# 09_Clock.net
KiCad netlist of a schematic drawn in Altium Designer
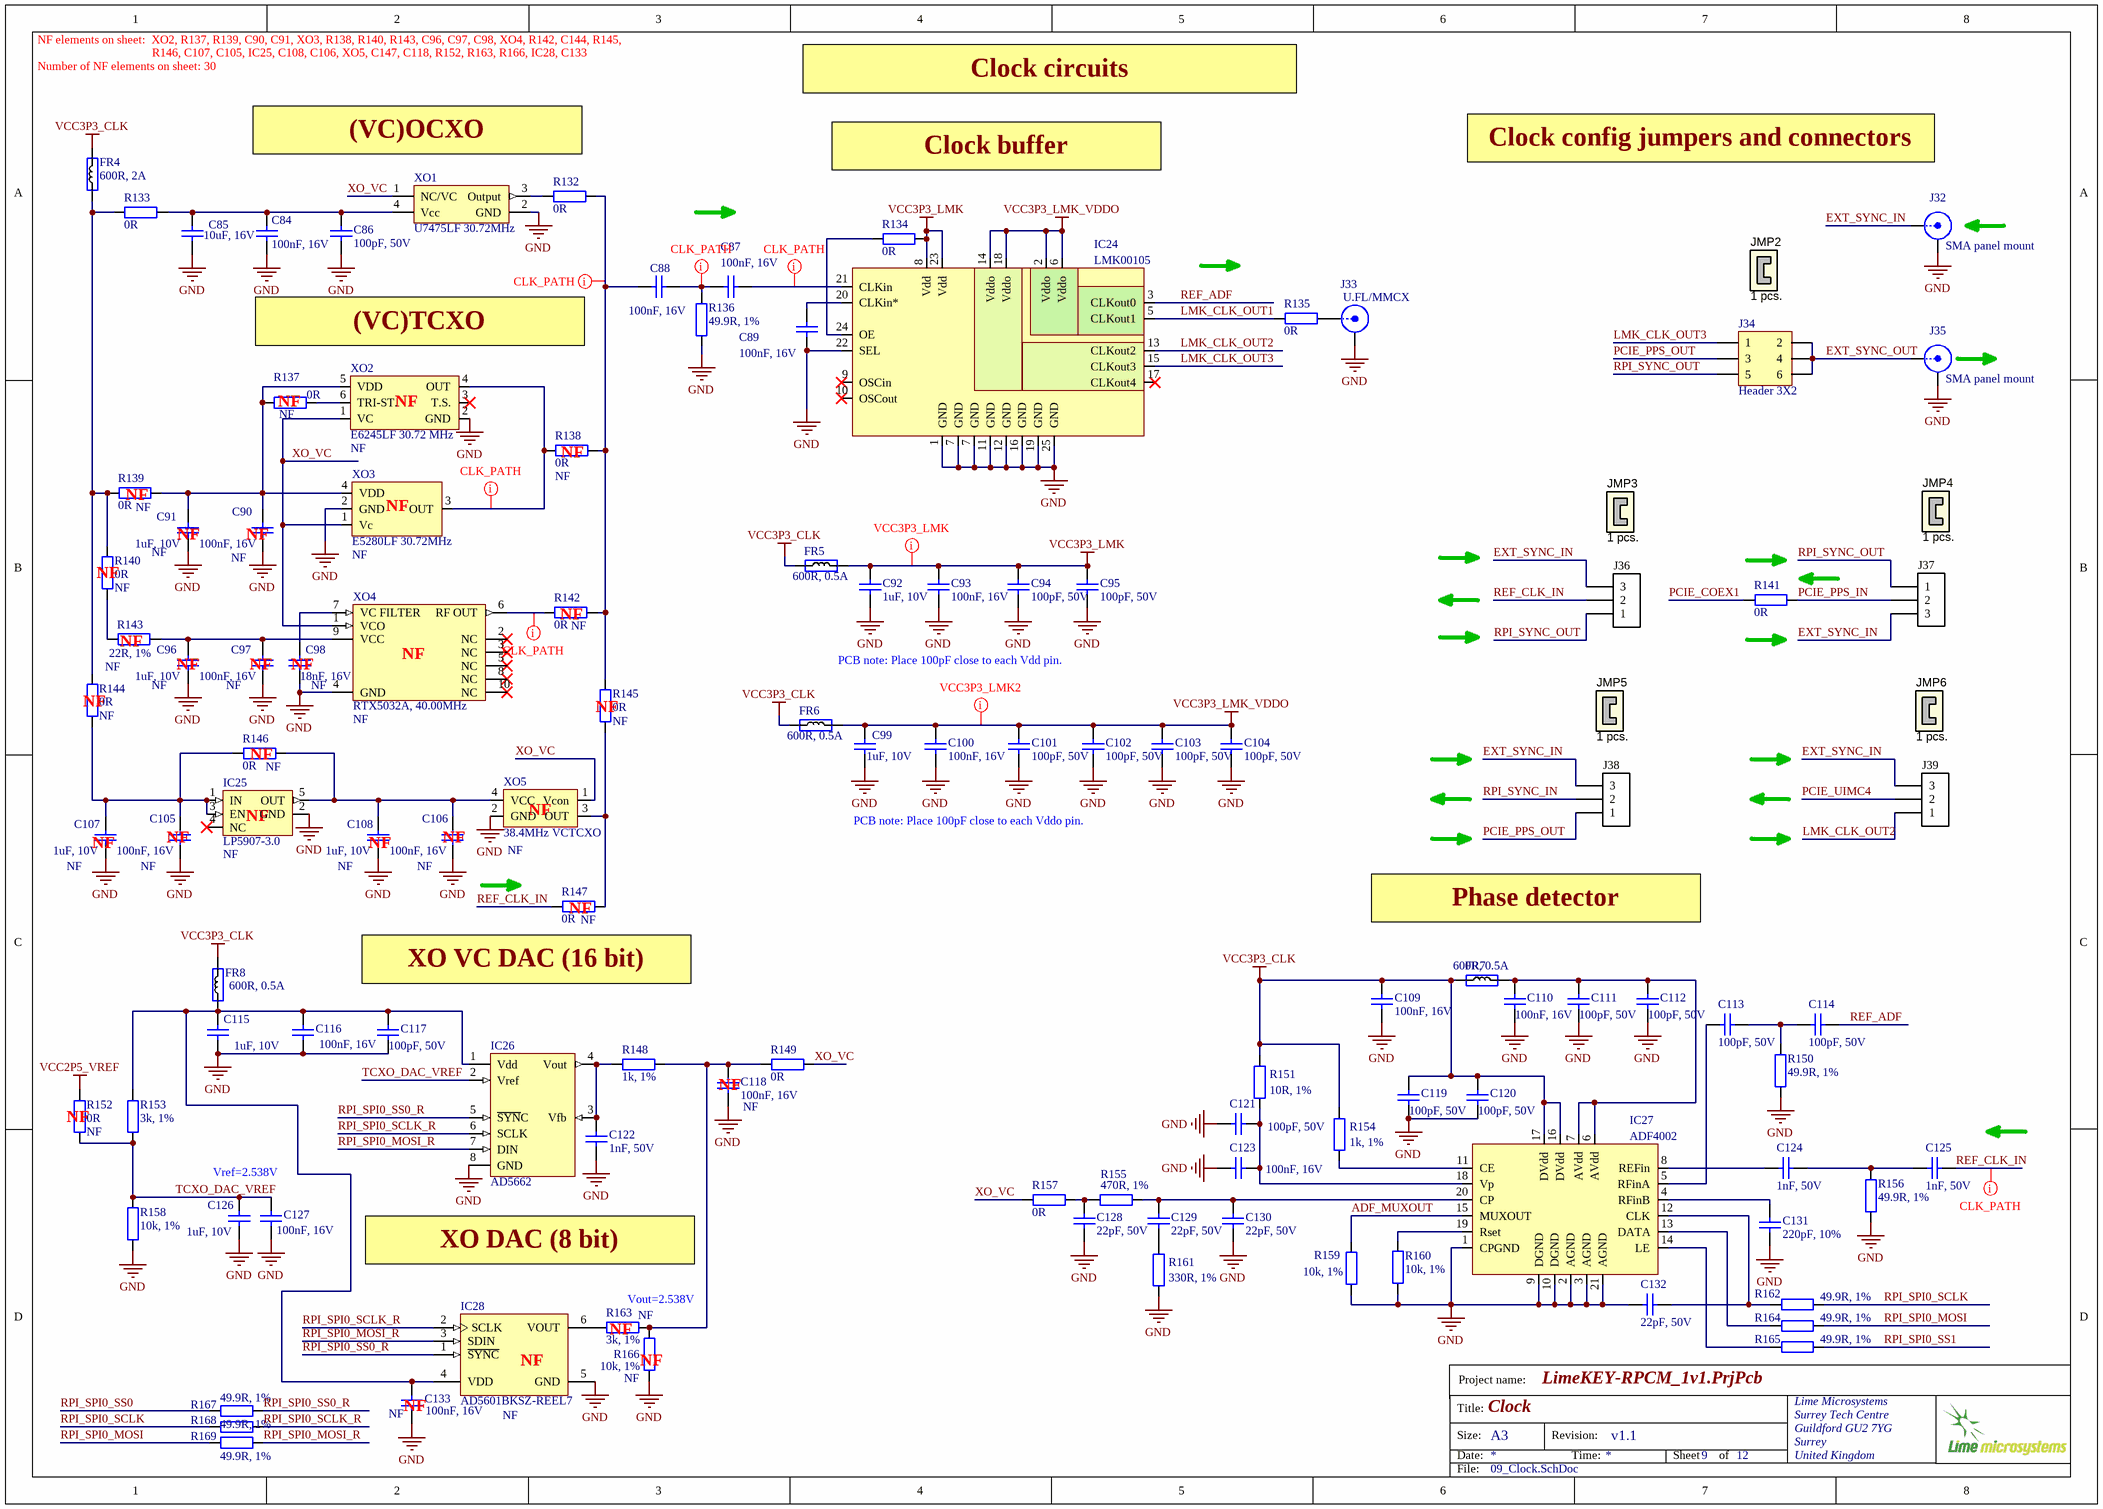
[diagram p0: 09_Clock.SchDoc]

(export (version "E")
  (design (tool "Eeschema 10.0.6"))
  (components
    (comp (ref "C84")
      (value "100nF, 16V")
      (footprint "CAP0402")
      (fields
        (field (name "MANUFACTURER") "Murata Electronics")
        (field (name "TOLERANCE") "10 %")
        (field (name "MANUFACTURER PART NUMBER") "GRM155R71C104KA88D")
      )
      (libsource (lib "LimeMicroAltiumLib_schLib") (part "Cap_0402"))
    )
    (comp (ref "C85")
      (value "10uF, 16V")
      (footprint "CAP0603")
      (fields (field (name "MANUFACTURER") "Yageo") (field (name "TOLERANCE") "±20%"))
      (libsource (lib "LimeMicroAltiumLib_schLib") (part "Cap_0603"))
    )
    (comp (ref "C86")
      (value "100pF, 50V")
      (footprint "CAP0402")
      (fields (field (name "TOLERANCE") "±5%") (field (name "MANUFACTURER") "Yageo"))
      (libsource (lib "LimeMicroAltiumLib_schLib") (part "Cap_0402"))
    )
    (comp (ref "C87")
      (value "100nF, 16V")
      (footprint "CAP0402")
      (fields
        (field (name "MANUFACTURER") "Murata Electronics")
        (field (name "TOLERANCE") "10 %")
        (field (name "MANUFACTURER PART NUMBER") "GRM155R71C104KA88D")
      )
      (libsource (lib "LimeMicroAltiumLib_schLib") (part "Cap_0402"))
    )
    (comp (ref "C88")
      (value "100nF, 16V")
      (footprint "CAP0402")
      (fields
        (field (name "MANUFACTURER") "Murata Electronics")
        (field (name "TOLERANCE") "10 %")
        (field (name "MANUFACTURER PART NUMBER") "GRM155R71C104KA88D")
      )
      (libsource (lib "LimeMicroAltiumLib_schLib") (part "Cap_0402"))
    )
    (comp (ref "C89")
      (value "100nF, 16V")
      (footprint "CAP0402")
      (fields
        (field (name "MANUFACTURER") "Murata Electronics")
        (field (name "TOLERANCE") "10 %")
        (field (name "MANUFACTURER PART NUMBER") "GRM155R71C104KA88D")
      )
      (libsource (lib "LimeMicroAltiumLib_schLib") (part "Cap_0402"))
    )
    (comp (ref "C90")
      (value "100nF, 16V")
      (footprint "CAP0402")
      (fields
        (field (name "ASSEMBLY INFO") "NF")
        (field (name "MANUFACTURER") "Murata Electronics")
        (field (name "TOLERANCE") "10 %")
        (field (name "MANUFACTURER PART NUMBER") "GRM155R71C104KA88D")
      )
      (libsource (lib "LimeMicroAltiumLib_schLib") (part "Cap_0402"))
    )
    (comp (ref "C91")
      (value "1uF, 10V")
      (footprint "CAP0402")
      (description "CAP CER 1UF 10V X5R 0402")
      (fields (field (name "ASSEMBLY INFO") "NF") (field (name "MANUFACTURER") "Yageo"))
      (libsource (lib "LimeMicroAltiumLib_schLib") (part "Cap_0402"))
    )
    (comp (ref "C92")
      (value "1uF, 10V")
      (footprint "CAP0402")
      (description "CAP CER 1UF 10V X5R 0402")
      (fields (field (name "MANUFACTURER") "Yageo") (field (name "TOLERANCE") "±20%"))
      (libsource (lib "LimeMicroAltiumLib_schLib") (part "Cap_0402"))
    )
    (comp (ref "C93")
      (value "100nF, 16V")
      (footprint "CAP0402")
      (fields
        (field (name "MANUFACTURER") "Murata Electronics")
        (field (name "TOLERANCE") "10 %")
        (field (name "MANUFACTURER PART NUMBER") "GRM155R71C104KA88D")
      )
      (libsource (lib "LimeMicroAltiumLib_schLib") (part "Cap_0402"))
    )
    (comp (ref "C94")
      (value "100pF, 50V")
      (footprint "CAP0402")
      (fields (field (name "MANUFACTURER") "Yageo") (field (name "TOLERANCE") "±5%"))
      (libsource (lib "LimeMicroAltiumLib_schLib") (part "Cap_0402"))
    )
    (comp (ref "C95")
      (value "100pF, 50V")
      (footprint "CAP0402")
      (fields (field (name "MANUFACTURER") "Yageo") (field (name "TOLERANCE") "±5%"))
      (libsource (lib "LimeMicroAltiumLib_schLib") (part "Cap_0402"))
    )
    (comp (ref "C96")
      (value "1uF, 10V")
      (footprint "CAP0402")
      (description "CAP CER 1UF 10V X5R 0402")
      (fields (field (name "ASSEMBLY INFO") "NF") (field (name "MANUFACTURER") "Yageo"))
      (libsource (lib "LimeMicroAltiumLib_schLib") (part "Cap_0402"))
    )
    (comp (ref "C97")
      (value "100nF, 16V")
      (footprint "CAP0402")
      (fields
        (field (name "ASSEMBLY INFO") "NF")
        (field (name "MANUFACTURER") "Murata Electronics")
        (field (name "TOLERANCE") "10 %")
        (field (name "MANUFACTURER PART NUMBER") "GRM155R71C104KA88D")
      )
      (libsource (lib "LimeMicroAltiumLib_schLib") (part "Cap_0402"))
    )
    (comp (ref "C98")
      (value "18nF, 16V")
      (footprint "CAP0402")
      (fields
        (field (name "ASSEMBLY INFO") "NF")
        (field (name "MANUFACTURER") "Yageo")
        (field (name "TOLERANCE") "±10%")
      )
      (libsource (lib "LimeMicroAltiumLib_schLib") (part "Cap_0402"))
    )
    (comp (ref "C99")
      (value "1uF, 10V")
      (footprint "CAP0402")
      (description "CAP CER 1UF 10V X5R 0402")
      (fields (field (name "MANUFACTURER") "Yageo") (field (name "TOLERANCE") "±20%"))
      (libsource (lib "LimeMicroAltiumLib_schLib") (part "Cap_0402"))
    )
    (comp (ref "C100")
      (value "100nF, 16V")
      (footprint "CAP0402")
      (fields
        (field (name "MANUFACTURER") "Murata Electronics")
        (field (name "TOLERANCE") "10 %")
        (field (name "MANUFACTURER PART NUMBER") "GRM155R71C104KA88D")
      )
      (libsource (lib "LimeMicroAltiumLib_schLib") (part "Cap_0402"))
    )
    (comp (ref "C101")
      (value "100pF, 50V")
      (footprint "CAP0402")
      (fields (field (name "MANUFACTURER") "Yageo") (field (name "TOLERANCE") "±5%"))
      (libsource (lib "LimeMicroAltiumLib_schLib") (part "Cap_0402"))
    )
    (comp (ref "C102")
      (value "100pF, 50V")
      (footprint "CAP0402")
      (fields (field (name "MANUFACTURER") "Yageo") (field (name "TOLERANCE") "±5%"))
      (libsource (lib "LimeMicroAltiumLib_schLib") (part "Cap_0402"))
    )
    (comp (ref "C103")
      (value "100pF, 50V")
      (footprint "CAP0402")
      (fields (field (name "MANUFACTURER") "Yageo") (field (name "TOLERANCE") "±5%"))
      (libsource (lib "LimeMicroAltiumLib_schLib") (part "Cap_0402"))
    )
    (comp (ref "C104")
      (value "100pF, 50V")
      (footprint "CAP0402")
      (fields (field (name "MANUFACTURER") "Yageo") (field (name "TOLERANCE") "±5%"))
      (libsource (lib "LimeMicroAltiumLib_schLib") (part "Cap_0402"))
    )
    (comp (ref "C105")
      (value "100nF, 16V")
      (footprint "CAP0402")
      (fields
        (field (name "ASSEMBLY INFO") "NF")
        (field (name "MANUFACTURER") "Murata Electronics")
        (field (name "TOLERANCE") "10 %")
        (field (name "MANUFACTURER PART NUMBER") "GRM155R71C104KA88D")
      )
      (libsource (lib "") (part "Cap_0402_1"))
    )
    (comp (ref "C106")
      (value "100nF, 16V")
      (footprint "CAP0402")
      (fields
        (field (name "ASSEMBLY INFO") "NF")
        (field (name "MANUFACTURER") "Murata Electronics")
        (field (name "TOLERANCE") "10 %")
        (field (name "MANUFACTURER PART NUMBER") "GRM155R71C104KA88D")
      )
      (libsource (lib "") (part "Cap_0402_1"))
    )
    (comp (ref "C107")
      (value "1uF, 10V")
      (footprint "CAP0402")
      (fields (field (name "ASSEMBLY INFO") "NF") (field (name "MANUFACTURER") "Yageo"))
      (libsource (lib "") (part "Cap_0402_1"))
    )
    (comp (ref "C108")
      (value "1uF, 10V")
      (footprint "CAP0402")
      (fields (field (name "ASSEMBLY INFO") "NF") (field (name "MANUFACTURER") "Yageo"))
      (libsource (lib "") (part "Cap_0402_1"))
    )
    (comp (ref "C109")
      (value "100nF, 16V")
      (footprint "CAP0402")
      (fields
        (field (name "MANUFACTURER") "Murata Electronics")
        (field (name "TOLERANCE") "10 %")
        (field (name "MANUFACTURER PART NUMBER") "GRM155R71C104KA88D")
      )
      (libsource (lib "LimeMicroAltiumLib_schLib") (part "Cap_0402"))
    )
    (comp (ref "C110")
      (value "100nF, 16V")
      (footprint "CAP0402")
      (fields
        (field (name "MANUFACTURER") "Murata Electronics")
        (field (name "TOLERANCE") "10 %")
        (field (name "MANUFACTURER PART NUMBER") "GRM155R71C104KA88D")
      )
      (libsource (lib "LimeMicroAltiumLib_schLib") (part "Cap_0402"))
    )
    (comp (ref "C111")
      (value "100pF, 50V")
      (footprint "CAP0402")
      (fields (field (name "MANUFACTURER") "Yageo") (field (name "TOLERANCE") "±5%"))
      (libsource (lib "LimeMicroAltiumLib_schLib") (part "Cap_0402"))
    )
    (comp (ref "C112")
      (value "100pF, 50V")
      (footprint "CAP0402")
      (fields (field (name "MANUFACTURER") "Yageo") (field (name "TOLERANCE") "±5%"))
      (libsource (lib "LimeMicroAltiumLib_schLib") (part "Cap_0402"))
    )
    (comp (ref "C113")
      (value "100pF, 50V")
      (footprint "CAP0402")
      (fields (field (name "MANUFACTURER") "Yageo") (field (name "TOLERANCE") "±5%"))
      (libsource (lib "LimeMicroAltiumLib_schLib") (part "Cap_0402"))
    )
    (comp (ref "C114")
      (value "100pF, 50V")
      (footprint "CAP0402")
      (fields (field (name "MANUFACTURER") "Yageo") (field (name "TOLERANCE") "±5%"))
      (libsource (lib "LimeMicroAltiumLib_schLib") (part "Cap_0402"))
    )
    (comp (ref "C115")
      (value "1uF, 10V")
      (footprint "CAP0402")
      (description "CAP CER 1UF 10V X5R 0402")
      (fields (field (name "MANUFACTURER") "Yageo") (field (name "TOLERANCE") "±20%"))
      (libsource (lib "LimeMicroAltiumLib_schLib") (part "Cap_0402"))
    )
    (comp (ref "C116")
      (value "100nF, 16V")
      (footprint "CAP0402")
      (fields
        (field (name "TOLERANCE") "10 %")
        (field (name "MANUFACTURER") "Murata Electronics")
        (field (name "MANUFACTURER PART NUMBER") "GRM155R71C104KA88D")
      )
      (libsource (lib "LimeFPGAboard_schLib") (part "Cap_0603"))
    )
    (comp (ref "C117")
      (value "100pF, 50V")
      (footprint "CAP0402")
      (fields (field (name "MANUFACTURER") "Yageo") (field (name "TOLERANCE") "±5%"))
      (libsource (lib "LimeMicroAltiumLib_schLib") (part "Cap_0402"))
    )
    (comp (ref "C118")
      (value "100nF, 16V")
      (footprint "CAP0402")
      (fields
        (field (name "ASSEMBLY INFO") "NF")
        (field (name "MANUFACTURER") "Murata Electronics")
        (field (name "TOLERANCE") "10 %")
        (field (name "MANUFACTURER PART NUMBER") "GRM155R71C104KA88D")
      )
      (libsource (lib "LimeMicroAltiumLib_schLib") (part "Cap_0402"))
    )
    (comp (ref "C119")
      (value "100pF, 50V")
      (footprint "CAP0402")
      (fields (field (name "MANUFACTURER") "Yageo") (field (name "TOLERANCE") "±5%"))
      (libsource (lib "LimeMicroAltiumLib_schLib") (part "Cap_0402"))
    )
    (comp (ref "C120")
      (value "100pF, 50V")
      (footprint "CAP0402")
      (fields (field (name "MANUFACTURER") "Yageo") (field (name "TOLERANCE") "±5%"))
      (libsource (lib "LimeMicroAltiumLib_schLib") (part "Cap_0402"))
    )
    (comp (ref "C121")
      (value "100pF, 50V")
      (footprint "CAP0402")
      (fields (field (name "MANUFACTURER") "Yageo") (field (name "TOLERANCE") "±5%"))
      (libsource (lib "LimeMicroAltiumLib_schLib") (part "Cap_0402"))
    )
    (comp (ref "C122")
      (value "1nF, 50V")
      (footprint "CAP0402")
      (fields
        (field (name "TOLERANCE") "±10%")
        (field (name "MANUFACTURER") "Murata Electronics North America")
      )
      (libsource (lib "LimeMicroAltiumLib_schLib") (part "Cap_0402"))
    )
    (comp (ref "C123")
      (value "100nF, 16V")
      (footprint "CAP0402")
      (fields
        (field (name "MANUFACTURER") "Murata Electronics")
        (field (name "TOLERANCE") "10 %")
        (field (name "MANUFACTURER PART NUMBER") "GRM155R71C104KA88D")
      )
      (libsource (lib "LimeMicroAltiumLib_schLib") (part "Cap_0402"))
    )
    (comp (ref "C124")
      (value "1nF, 50V")
      (footprint "CAP0402")
      (fields
        (field (name "TOLERANCE") "±10%")
        (field (name "MANUFACTURER") "Murata Electronics North America")
      )
      (libsource (lib "LimeMicroAltiumLib_schLib") (part "Cap_0402"))
    )
    (comp (ref "C125")
      (value "1nF, 50V")
      (footprint "CAP0402")
      (fields
        (field (name "TOLERANCE") "±10%")
        (field (name "MANUFACTURER") "Murata Electronics North America")
      )
      (libsource (lib "LimeMicroAltiumLib_schLib") (part "Cap_0402"))
    )
    (comp (ref "C126")
      (value "1uF, 10V")
      (footprint "CAP0402")
      (description "CAP CER 1UF 10V X5R 0402")
      (fields (field (name "MANUFACTURER") "Yageo") (field (name "TOLERANCE") "±20%"))
      (libsource (lib "LimeMicroAltiumLib_schLib") (part "Cap_0402"))
    )
    (comp (ref "C127")
      (value "100nF, 16V")
      (footprint "CAP0402")
      (fields
        (field (name "TOLERANCE") "10 %")
        (field (name "MANUFACTURER") "Murata Electronics")
        (field (name "MANUFACTURER PART NUMBER") "GRM155R71C104KA88D")
      )
      (libsource (lib "LimeFPGAboard_schLib") (part "Cap_0603"))
    )
    (comp (ref "C128")
      (value "22pF, 50V")
      (footprint "CAP0402")
      (fields (field (name "TOLERANCE") "±5%") (field (name "MANUFACTURER") "Yageo"))
      (libsource (lib "LimeMicroAltiumLib_schLib") (part "Cap_0402"))
    )
    (comp (ref "C129")
      (value "22pF, 50V")
      (footprint "CAP0402")
      (fields (field (name "TOLERANCE") "±5%") (field (name "MANUFACTURER") "Yageo"))
      (libsource (lib "LimeMicroAltiumLib_schLib") (part "Cap_0402"))
    )
    (comp (ref "C130")
      (value "22pF, 50V")
      (footprint "CAP0402")
      (fields (field (name "TOLERANCE") "±5%") (field (name "MANUFACTURER") "Yageo"))
      (libsource (lib "LimeMicroAltiumLib_schLib") (part "Cap_0402"))
    )
    (comp (ref "C131")
      (value "220pF, 10%")
      (footprint "CAP0402")
      (fields (field (name "MANUFACTURER") "Yageo") (field (name "TOLERANCE") "±10%"))
      (libsource (lib "LimeMicroAltiumLib_schLib") (part "Cap_0402"))
    )
    (comp (ref "C132")
      (value "22pF, 50V")
      (footprint "CAP0402")
      (fields (field (name "TOLERANCE") "±5%") (field (name "MANUFACTURER") "Yageo"))
      (libsource (lib "LimeMicroAltiumLib_schLib") (part "Cap_0402"))
    )
    (comp (ref "C133")
      (value "100nF, 16V")
      (footprint "CAP0402")
      (fields
        (field (name "TOLERANCE") "10 %")
        (field (name "MANUFACTURER") "Murata Electronics")
        (field (name "MANUFACTURER PART NUMBER") "GRM155R71C104KA88D")
        (field (name "ASSEMBLY INFO") "NF")
      )
      (libsource (lib "LimeFPGAboard_schLib") (part "Cap_0603"))
    )
    (comp (ref "FR4")
      (value "600R, 2A")
      (footprint "RES0805")
      (fields (field (name "MANUFACTURER") "TDK Corporation"))
      (libsource (lib "LimeFPGAboard_schLib") (part "Ferrite"))
    )
    (comp (ref "FR5")
      (value "600R, 0.5A")
      (footprint "RES0402")
      (fields (field (name "MANUFACTURER") "Murata") (field (name "TOLERANCE") "25%"))
      (libsource (lib "LimeMicroAltiumLib_schLib") (part "Ferrite"))
    )
    (comp (ref "FR6")
      (value "600R, 0.5A")
      (footprint "RES0402")
      (fields (field (name "MANUFACTURER") "Murata") (field (name "TOLERANCE") "25%"))
      (libsource (lib "LimeMicroAltiumLib_schLib") (part "Ferrite"))
    )
    (comp (ref "FR7")
      (value "600R, 0.5A")
      (footprint "RES0402")
      (fields (field (name "MANUFACTURER") "Murata") (field (name "TOLERANCE") "25%"))
      (libsource (lib "LimeMicroAltiumLib_schLib") (part "Ferrite"))
    )
    (comp (ref "FR8")
      (value "600R, 0.5A")
      (footprint "RES0402")
      (fields (field (name "MANUFACTURER") "Murata") (field (name "TOLERANCE") "25%"))
      (libsource (lib "LimeMicroAltiumLib_schLib") (part "Ferrite"))
    )
    (comp (ref "IC24")
      (value "LMK00105")
      (footprint "LMK00105SQ")
      (fields (field (name "MANUFACTURER") "Texas Instruments"))
      (libsource (lib "LimeMicroAltiumLib_schLib") (part "LMK00105"))
    )
    (comp (ref "IC25")
      (value "LP5907-3.0")
      (footprint "SOT23-5")
      (fields (field (name "MANUFACTURER") "Texas Instruments") (field (name "ASSEMBLY INFO") "NF"))
      (libsource (lib "LimeMicroAltiumLib_schLib_r01") (part "LP5907"))
    )
    (comp (ref "IC26")
      (value "AD5662")
      (footprint "AD5662_SOT23-8")
      (fields (field (name "MANUFACTURER") "Analog Devices Inc."))
      (libsource (lib "LimeMicroAltiumLib_schLib") (part "AD5662"))
    )
    (comp (ref "IC27")
      (value "ADF4002")
      (footprint "ADF4002")
      (fields (field (name "MANUFACTURER") "Analog Devices Inc"))
      (libsource (lib "LimeMicroAltiumLib_schLib") (part "ADF4002"))
    )
    (comp (ref "IC28")
      (value "AD5601BKSZ-REEL7")
      (footprint "AD5601_SOT23-6")
      (fields
        (field (name "GENERIC PART NUMBER") "AD5601")
        (field (name "MANUFACTURER") "Analog Devices")
        (field (name "ASSEMBLY INFO") "NF")
      )
      (libsource (lib "LimeMicroAltiumLib_schLib") (part "AD5601BKSZ-REEL7"))
    )
    (comp (ref "J32")
      (value "SMA panel mount")
      (footprint "SMA_connector_side")
      (description "CONN SMA JACK STR 50OHM EDGE MNT")
      (fields (field (name "MANUFACTURER") "Linx"))
      (libsource (lib "") (part "RF_IF_connector_1"))
    )
    (comp (ref "J33")
      (value "U.FL/MMCX")
      (footprint "MMCX_UFL_conn_u")
      (description "CONN UMC RCPT STR 50 OHM SMD")
      (fields (field (name "MANUFACTURER") "Molex, LLC"))
      (libsource (lib "LimeMicroAltiumLib_schLib") (part "RF_IF_connector"))
    )
    (comp (ref "J34")
      (value "Header 3X2")
      (footprint "Header3x2")
      (description "Header, 2-Pin, Dual row")
      (fields
        (field (name "MANUFACTURER PART NUMBER") "PH2-06-UA")
        (field (name "MANUFACTURER") "Adam Equipment")
      )
      (libsource (lib "LimeMicroAltiumLib_schLib_r01") (part "Header 3X2"))
    )
    (comp (ref "J35")
      (value "SMA panel mount")
      (footprint "SMA_connector_side")
      (description "CONN SMA JACK STR 50OHM EDGE MNT")
      (fields (field (name "MANUFACTURER") "Linx"))
      (libsource (lib "") (part "RF_IF_connector_1"))
    )
    (comp (ref "J36")
      (value "Header 3x1 pin")
      (footprint "HDR_1x3")
      (description "Header, 3-pin")
      (fields
        (field (name "MANUFACTURER PART NUMBER") "61300311121")
        (field (name "MANUFACTURER") "Wurth Electronics")
      )
      (libsource (lib "LimeMicroAltiumLib_schLib_r04") (part "Header3P"))
    )
    (comp (ref "J37")
      (value "Header 3x1 pin")
      (footprint "HDR_1x3")
      (description "Header, 3-pin")
      (fields
        (field (name "MANUFACTURER PART NUMBER") "61300311121")
        (field (name "MANUFACTURER") "Wurth Electronics")
      )
      (libsource (lib "") (part "Header3P_1"))
    )
    (comp (ref "J38")
      (value "Header 3x1 pin")
      (footprint "HDR_1x3")
      (description "Header, 3-pin")
      (fields
        (field (name "MANUFACTURER PART NUMBER") "61300311121")
        (field (name "MANUFACTURER") "Wurth Electronics")
      )
      (libsource (lib "LimeMicroAltiumLib_schLib_r04") (part "Header3P"))
    )
    (comp (ref "J39")
      (value "Header 3x1 pin")
      (footprint "HDR_1x3")
      (description "Header, 3-pin")
      (fields
        (field (name "MANUFACTURER PART NUMBER") "61300311121")
        (field (name "MANUFACTURER") "Wurth Electronics")
      )
      (libsource (lib "LimeMicroAltiumLib_schLib_r04") (part "Header3P"))
    )
    (comp (ref "JMP2")
      (value "1 pcs.")
      (description "Shorting Jumper, 2-position, 1.27mm pitch")
      (fields (field (name "MANUFACTURER") "Sullins"))
      (libsource (lib "LimeMicroAltiumLib_schLib") (part "JUMP_2P_CONN_HEADER"))
    )
    (comp (ref "JMP3")
      (value "1 pcs.")
      (description "Shorting Jumper, 2-position, 1.27mm pitch")
      (fields (field (name "MANUFACTURER") "Sullins"))
      (libsource (lib "LimeMicroAltiumLib_schLib") (part "JUMP_2P_CONN_HEADER"))
    )
    (comp (ref "JMP4")
      (value "1 pcs.")
      (description "Shorting Jumper, 2-position, 1.27mm pitch")
      (fields (field (name "MANUFACTURER") "Sullins"))
      (libsource (lib "LimeMicroAltiumLib_schLib") (part "JUMP_2P_CONN_HEADER"))
    )
    (comp (ref "JMP5")
      (value "1 pcs.")
      (description "Shorting Jumper, 2-position, 1.27mm pitch")
      (fields (field (name "MANUFACTURER") "Sullins"))
      (libsource (lib "LimeMicroAltiumLib_schLib") (part "JUMP_2P_CONN_HEADER"))
    )
    (comp (ref "JMP6")
      (value "1 pcs.")
      (description "Shorting Jumper, 2-position, 1.27mm pitch")
      (fields (field (name "MANUFACTURER") "Sullins"))
      (libsource (lib "LimeMicroAltiumLib_schLib") (part "JUMP_2P_CONN_HEADER"))
    )
    (comp (ref "R132")
      (value "0R")
      (footprint "RES0402_v2")
      (fields (field (name "MANUFACTURER") "Yageo") (field (name "TOLERANCE") "Jumper"))
      (libsource (lib "LimeMicroAltiumLib_schLib") (part "Res_0402"))
    )
    (comp (ref "R133")
      (value "0R")
      (footprint "RES0402")
      (fields (field (name "MANUFACTURER") "Yageo") (field (name "TOLERANCE") "Jumper"))
      (libsource (lib "LimeMicroAltiumLib_schLib") (part "Res_0402"))
    )
    (comp (ref "R134")
      (value "0R")
      (footprint "RES0402")
      (fields (field (name "MANUFACTURER") "Yageo") (field (name "TOLERANCE") "Jumper"))
      (libsource (lib "LimeMicroAltiumLib_schLib") (part "Res_0402"))
    )
    (comp (ref "R135")
      (value "0R")
      (footprint "RES0402")
      (fields (field (name "MANUFACTURER") "Yageo") (field (name "TOLERANCE") "Jumper"))
      (libsource (lib "") (part "Res_0402_1"))
    )
    (comp (ref "R136")
      (value "49.9R, 1%")
      (footprint "RES0402")
      (fields
        (field (name "TOLERANCE") "±1%")
        (field (name "MANUFACTURER") "Samsung Electro-Mechanics America, Inc.")
      )
      (libsource (lib "LimeMicroAltiumLib_schLib") (part "Res_0402"))
    )
    (comp (ref "R137")
      (value "0R")
      (footprint "RES0402")
      (fields
        (field (name "ASSEMBLY INFO") "NF")
        (field (name "MANUFACTURER") "Yageo")
        (field (name "TOLERANCE") "Jumper")
      )
      (libsource (lib "LimeMicroAltiumLib_schLib") (part "Res_0402"))
    )
    (comp (ref "R138")
      (value "0R")
      (footprint "RES0402_v2")
      (fields
        (field (name "ASSEMBLY INFO") "NF")
        (field (name "MANUFACTURER") "Yageo")
        (field (name "TOLERANCE") "Jumper")
      )
      (libsource (lib "LimeMicroAltiumLib_schLib") (part "Res_0402"))
    )
    (comp (ref "R139")
      (value "0R")
      (footprint "RES0402")
      (fields
        (field (name "MANUFACTURER") "Yageo")
        (field (name "TOLERANCE") "Jumper")
        (field (name "ASSEMBLY INFO") "NF")
      )
      (libsource (lib "LimeMicroAltiumLib_schLib") (part "Res_0402"))
    )
    (comp (ref "R140")
      (value "0R")
      (footprint "RES0402")
      (fields
        (field (name "ASSEMBLY INFO") "NF")
        (field (name "MANUFACTURER") "Yageo")
        (field (name "TOLERANCE") "Jumper")
      )
      (libsource (lib "LimeMicroAltiumLib_schLib") (part "Res_0402"))
    )
    (comp (ref "R141")
      (value "0R")
      (footprint "RES0402")
      (fields (field (name "MANUFACTURER") "Yageo") (field (name "TOLERANCE") "Jumper"))
      (libsource (lib "") (part "Res_0402_1"))
    )
    (comp (ref "R142")
      (value "0R")
      (footprint "RES0402_v2")
      (fields
        (field (name "ASSEMBLY INFO") "NF")
        (field (name "MANUFACTURER") "Yageo")
        (field (name "TOLERANCE") "Jumper")
      )
      (libsource (lib "LimeMicroAltiumLib_schLib") (part "Res_0402"))
    )
    (comp (ref "R143")
      (value "22R, 1%")
      (footprint "RES0402")
      (fields
        (field (name "TOLERANCE") "±1%")
        (field (name "MANUFACTURER") "Yageo")
        (field (name "ASSEMBLY INFO") "NF")
      )
      (libsource (lib "LimeFPGAboard_schLib") (part "Res_0402"))
    )
    (comp (ref "R144")
      (value "0R")
      (footprint "RES0402")
      (fields
        (field (name "MANUFACTURER") "Yageo")
        (field (name "TOLERANCE") "Jumper")
        (field (name "ASSEMBLY INFO") "NF")
      )
      (libsource (lib "") (part "Res_0402_1"))
    )
    (comp (ref "R145")
      (value "0R")
      (footprint "RES0402_v2")
      (fields
        (field (name "ASSEMBLY INFO") "NF")
        (field (name "MANUFACTURER") "Yageo")
        (field (name "TOLERANCE") "Jumper")
      )
      (libsource (lib "") (part "Res_0402_1"))
    )
    (comp (ref "R146")
      (value "0R")
      (footprint "RES0402")
      (fields
        (field (name "MANUFACTURER") "Yageo")
        (field (name "TOLERANCE") "Jumper")
        (field (name "ASSEMBLY INFO") "NF")
      )
      (libsource (lib "") (part "Res_0402_1"))
    )
    (comp (ref "R147")
      (value "0R")
      (footprint "RES0402_v2")
      (fields
        (field (name "ASSEMBLY INFO") "NF")
        (field (name "MANUFACTURER") "Yageo")
        (field (name "TOLERANCE") "Jumper")
      )
      (libsource (lib "LimeMicroAltiumLib_schLib") (part "Res_0402"))
    )
    (comp (ref "R148")
      (value "1k, 1%")
      (footprint "RES0402")
      (fields (field (name "MANUFACTURER") "Stackpole Electronics Inc") (field (name "TOLERANCE") "±1%"))
      (libsource (lib "LimeMicroAltiumLib_schLib") (part "Res_0402"))
    )
    (comp (ref "R149")
      (value "0R")
      (footprint "RES0402")
      (fields (field (name "MANUFACTURER") "Yageo") (field (name "TOLERANCE") "Jumper"))
      (libsource (lib "LimeMicroAltiumLib_schLib") (part "Res_0402"))
    )
    (comp (ref "R150")
      (value "49.9R, 1%")
      (footprint "RES0402")
      (fields
        (field (name "TOLERANCE") "±1%")
        (field (name "MANUFACTURER") "Samsung Electro-Mechanics America, Inc.")
      )
      (libsource (lib "LimeMicroAltiumLib_schLib") (part "Res_0402"))
    )
    (comp (ref "R151")
      (value "10R, 1%")
      (footprint "RES0402")
      (fields (field (name "MANUFACTURER") "Stackpole Electronics") (field (name "TOLERANCE") "1%"))
      (libsource (lib "LimeMicroAltiumLib_schLib") (part "Res_0402"))
    )
    (comp (ref "R152")
      (value "0R")
      (footprint "RES0402_v2")
      (fields
        (field (name "ASSEMBLY INFO") "NF")
        (field (name "MANUFACTURER") "Yageo")
        (field (name "TOLERANCE") "Jumper")
      )
      (libsource (lib "LimeMicroAltiumLib_schLib") (part "Res_0402"))
    )
    (comp (ref "R153")
      (value "3k, 1%")
      (footprint "RES0402")
      (fields (field (name "TOLERANCE") "±1%") (field (name "MANUFACTURER") "Vishay Dale"))
      (libsource (lib "LimeMicroAltiumLib_schLib") (part "Res_0402"))
    )
    (comp (ref "R154")
      (value "1k, 1%")
      (footprint "RES0402")
      (fields (field (name "MANUFACTURER") "Stackpole Electronics Inc") (field (name "TOLERANCE") "±1%"))
      (libsource (lib "LimeMicroAltiumLib_schLib") (part "Res_0402"))
    )
    (comp (ref "R155")
      (value "470R, 1%")
      (footprint "RES0402")
      (fields (field (name "TOLERANCE") "1%") (field (name "MANUFACTURER") "Yageo"))
      (libsource (lib "") (part "Res_0402_1"))
    )
    (comp (ref "R156")
      (value "49.9R, 1%")
      (footprint "RES0402")
      (fields
        (field (name "TOLERANCE") "±1%")
        (field (name "MANUFACTURER") "Samsung Electro-Mechanics America, Inc.")
      )
      (libsource (lib "LimeMicroAltiumLib_schLib") (part "Res_0402"))
    )
    (comp (ref "R157")
      (value "0R")
      (footprint "RES0402")
      (fields (field (name "MANUFACTURER") "Yageo") (field (name "TOLERANCE") "Jumper"))
      (libsource (lib "LimeMicroAltiumLib_schLib") (part "Res_0402"))
    )
    (comp (ref "R158")
      (value "10k, 1%")
      (footprint "RES0402")
      (fields (field (name "MANUFACTURER") "Yageo") (field (name "TOLERANCE") "±1%"))
      (libsource (lib "LimeMicroAltiumLib_schLib") (part "Res_0402"))
    )
    (comp (ref "R159")
      (value "10k, 1%")
      (footprint "RES0402")
      (fields (field (name "MANUFACTURER") "Yageo") (field (name "TOLERANCE") "±1%"))
      (libsource (lib "LimeMicroAltiumLib_schLib") (part "Res_0402"))
    )
    (comp (ref "R160")
      (value "10k, 1%")
      (footprint "RES0402")
      (fields (field (name "MANUFACTURER") "Yageo") (field (name "TOLERANCE") "±1%"))
      (libsource (lib "LimeMicroAltiumLib_schLib") (part "Res_0402"))
    )
    (comp (ref "R161")
      (value "330R, 1%")
      (footprint "RES0402")
      (fields (field (name "MANUFACTURER") "Yageo") (field (name "TOLERANCE") "1%"))
      (libsource (lib "LimeMicroAltiumLib_schLib") (part "Res_0402"))
    )
    (comp (ref "R162")
      (value "49.9R, 1%")
      (footprint "RES0402")
      (fields
        (field (name "TOLERANCE") "±1%")
        (field (name "MANUFACTURER") "Samsung Electro-Mechanics America, Inc.")
      )
      (libsource (lib "LimeMicroAltiumLib_schLib") (part "Res_0402"))
    )
    (comp (ref "R163")
      (value "3k, 1%")
      (footprint "RES0402")
      (fields
        (field (name "ASSEMBLY INFO") "NF")
        (field (name "TOLERANCE") "±1%")
        (field (name "MANUFACTURER") "Vishay Dale")
      )
      (libsource (lib "LimeMicroAltiumLib_schLib") (part "Res_0402"))
    )
    (comp (ref "R164")
      (value "49.9R, 1%")
      (footprint "RES0402")
      (fields
        (field (name "TOLERANCE") "±1%")
        (field (name "MANUFACTURER") "Samsung Electro-Mechanics America, Inc.")
      )
      (libsource (lib "LimeMicroAltiumLib_schLib") (part "Res_0402"))
    )
    (comp (ref "R165")
      (value "49.9R, 1%")
      (footprint "RES0402")
      (fields
        (field (name "TOLERANCE") "±1%")
        (field (name "MANUFACTURER") "Samsung Electro-Mechanics America, Inc.")
      )
      (libsource (lib "LimeMicroAltiumLib_schLib") (part "Res_0402"))
    )
    (comp (ref "R166")
      (value "10k, 1%")
      (footprint "RES0402")
      (fields
        (field (name "ASSEMBLY INFO") "NF")
        (field (name "MANUFACTURER") "Yageo")
        (field (name "TOLERANCE") "±1%")
      )
      (libsource (lib "LimeMicroAltiumLib_schLib") (part "Res_0402"))
    )
    (comp (ref "R167")
      (value "49.9R, 1%")
      (footprint "RES0402")
      (fields
        (field (name "TOLERANCE") "±1%")
        (field (name "MANUFACTURER") "Samsung Electro-Mechanics America, Inc.")
      )
      (libsource (lib "LimeMicroAltiumLib_schLib") (part "Res_0402"))
    )
    (comp (ref "R168")
      (value "49.9R, 1%")
      (footprint "RES0402")
      (fields
        (field (name "TOLERANCE") "±1%")
        (field (name "MANUFACTURER") "Samsung Electro-Mechanics America, Inc.")
      )
      (libsource (lib "LimeMicroAltiumLib_schLib") (part "Res_0402"))
    )
    (comp (ref "R169")
      (value "49.9R, 1%")
      (footprint "RES0402")
      (fields
        (field (name "TOLERANCE") "±1%")
        (field (name "MANUFACTURER") "Samsung Electro-Mechanics America, Inc.")
      )
      (libsource (lib "LimeMicroAltiumLib_schLib") (part "Res_0402"))
    )
    (comp (ref "XO1")
      (value "U7475LF 30.72MHz")
      (footprint "AOCJYR-10.000MHz")
      (fields (field (name "MANUFACTURER") "Rakon"))
      (libsource (lib "LimeMicroAltiumLib_schLib") (part "AOCJYR-10.000MHz"))
    )
    (comp (ref "XO2")
      (value "E6245LF 30.72 MHz")
      (footprint "RAKON_RPT7050A")
      (fields (field (name "ASSEMBLY INFO") "NF") (field (name "MANUFACTURER") "Rakon"))
      (libsource (lib "LimeMicroAltiumLib_schLib") (part "RPT7050A"))
    )
    (comp (ref "XO3")
      (value "E5280LF 30.72MHz")
      (footprint "RAKON_TXCO")
      (fields (field (name "ASSEMBLY INFO") "NF") (field (name "MANUFACTURER") "Rakon"))
      (libsource (lib "LimeMicroAltiumLib_schLib") (part "TXCO"))
    )
    (comp (ref "XO4")
      (value "RTX5032A, 40.00MHz")
      (footprint "RAKON_RTX5032A")
      (fields (field (name "ASSEMBLY INFO") "NF") (field (name "MANUFACTURER") "Rakon"))
      (libsource (lib "LimeMicroAltiumLib_schLib") (part "Rakon_RTX5032A"))
    )
    (comp (ref "XO5")
      (value "38.4MHz VCTCXO")
      (footprint "CRYSTAL_4-LCC_2P5x2P0")
      (description "Oscillator Crystal")
      (fields (field (name "MANUFACTURER") "Abracon") (field (name "ASSEMBLY INFO") "NF"))
      (libsource (lib "LimeMicroAltiumLib_schLib_r01") (part "ASVTX-12-A-38.400MHZ-H10-T_CRYSTAL"))
    )
  )
  (nets
    (net (code "1") (name "/ADF_MUXOUT") (class "Default")
      (node (ref "IC27") (pin "15") (pinfunction "MUXOUT_15") (pintype "passive"))
      (node (ref "R159") (pin "1") (pinfunction "1_1") (pintype "passive"))
    )
    (net (code "2") (name "/EXT_SYNC_IN") (class "Default")
      (node (ref "J32") (pin "1") (pinfunction "X_1") (pintype "passive"))
      (node (ref "J36") (pin "3") (pinfunction "3_3") (pintype "passive"))
      (node (ref "J37") (pin "3") (pinfunction "3_3") (pintype "passive"))
      (node (ref "J38") (pin "3") (pinfunction "3_3") (pintype "passive"))
      (node (ref "J39") (pin "3") (pinfunction "3_3") (pintype "passive"))
    )
    (net (code "3") (name "/EXT_SYNC_OUT") (class "Default")
      (node (ref "J34") (pin "2") (pinfunction "2_2") (pintype "passive"))
      (node (ref "J34") (pin "4") (pinfunction "4_4") (pintype "passive"))
      (node (ref "J34") (pin "6") (pinfunction "6_6") (pintype "passive"))
      (node (ref "J35") (pin "1") (pinfunction "X_1") (pintype "passive"))
    )
    (net (code "4") (name "/LMK_CLK_OUT1") (class "Default")
      (node (ref "IC24") (pin "5") (pinfunction "CLKout1_5") (pintype "passive"))
      (node (ref "R135") (pin "2") (pinfunction "2_2") (pintype "passive"))
    )
    (net (code "5") (name "/LMK_CLK_OUT2") (class "Default")
      (node (ref "IC24") (pin "13") (pinfunction "CLKout2_13") (pintype "passive"))
      (node (ref "J39") (pin "1") (pinfunction "1_1") (pintype "passive"))
    )
    (net (code "6") (name "/LMK_CLK_OUT3") (class "Default")
      (node (ref "IC24") (pin "15") (pinfunction "CLKout3_15") (pintype "passive"))
      (node (ref "J34") (pin "1") (pinfunction "1_1") (pintype "passive"))
    )
    (net (code "7") (name "/PCIE_COEX1") (class "Default")
      (node (ref "R141") (pin "2") (pinfunction "2_2") (pintype "passive"))
    )
    (net (code "9") (name "/PCIE_PPS_OUT") (class "Default")
      (node (ref "J34") (pin "3") (pinfunction "3_3") (pintype "passive"))
      (node (ref "J38") (pin "1") (pinfunction "1_1") (pintype "passive"))
    )
    (net (code "10") (name "/PCIE_UIMC4") (class "Default")
      (node (ref "J39") (pin "2") (pinfunction "2_2") (pintype "passive"))
    )
    (net (code "11") (name "/REF_ADF") (class "Default")
      (node (ref "C114") (pin "2") (pinfunction "2_2") (pintype "passive"))
      (node (ref "IC24") (pin "3") (pinfunction "CLKout0_3") (pintype "passive"))
    )
    (net (code "12") (name "/REF_CLK_IN") (class "Default")
      (node (ref "C125") (pin "2") (pinfunction "2_2") (pintype "passive"))
      (node (ref "J36") (pin "2") (pinfunction "2_2") (pintype "passive"))
      (node (ref "R147") (pin "2") (pinfunction "2_2") (pintype "passive"))
    )
    (net (code "13") (name "/RPI_SPI0_MOSI") (class "Default")
      (node (ref "R164") (pin "1") (pinfunction "1_1") (pintype "passive"))
      (node (ref "R169") (pin "2") (pinfunction "2_2") (pintype "passive"))
    )
    (net (code "14") (name "/RPI_SPI0_MOSI_R") (class "Default")
      (node (ref "IC26") (pin "7") (pinfunction "DIN_7") (pintype "input"))
      (node (ref "IC28") (pin "3") (pinfunction "SDIN_3") (pintype "input"))
      (node (ref "R169") (pin "1") (pinfunction "1_1") (pintype "passive"))
    )
    (net (code "15") (name "/RPI_SPI0_SCLK") (class "Default")
      (node (ref "R162") (pin "1") (pinfunction "1_1") (pintype "passive"))
      (node (ref "R168") (pin "2") (pinfunction "2_2") (pintype "passive"))
    )
    (net (code "16") (name "/RPI_SPI0_SCLK_R") (class "Default")
      (node (ref "IC26") (pin "6") (pinfunction "SCLK_6") (pintype "input"))
      (node (ref "IC28") (pin "2") (pinfunction "SCLK_2") (pintype "input"))
      (node (ref "R168") (pin "1") (pinfunction "1_1") (pintype "passive"))
    )
    (net (code "17") (name "/RPI_SPI0_SS0") (class "Default")
      (node (ref "R167") (pin "2") (pinfunction "2_2") (pintype "passive"))
    )
    (net (code "18") (name "/RPI_SPI0_SS0_R") (class "Default")
      (node (ref "IC26") (pin "5") (pinfunction "~{SYN}C_5") (pintype "input"))
      (node (ref "IC28") (pin "1") (pinfunction "~{SYNC}_1") (pintype "input"))
      (node (ref "R167") (pin "1") (pinfunction "1_1") (pintype "passive"))
    )
    (net (code "19") (name "/RPI_SPI0_SS1") (class "Default")
      (node (ref "R165") (pin "1") (pinfunction "1_1") (pintype "passive"))
    )
    (net (code "20") (name "/RPI_SYNC_IN") (class "Default")
      (node (ref "J38") (pin "2") (pinfunction "2_2") (pintype "passive"))
    )
    (net (code "21") (name "/RPI_SYNC_OUT") (class "Default")
      (node (ref "J34") (pin "5") (pinfunction "5_5") (pintype "passive"))
      (node (ref "J36") (pin "1") (pinfunction "1_1") (pintype "passive"))
      (node (ref "J37") (pin "1") (pinfunction "1_1") (pintype "passive"))
    )
    (net (code "22") (name "/TCXO_DAC_VREF") (class "Default")
      (node (ref "C126") (pin "2") (pinfunction "2_2") (pintype "passive"))
      (node (ref "C127") (pin "1") (pinfunction "1_1") (pintype "passive"))
      (node (ref "IC26") (pin "2") (pinfunction "Vref_2") (pintype "input"))
      (node (ref "R152") (pin "1") (pinfunction "1_1") (pintype "passive"))
      (node (ref "R153") (pin "1") (pinfunction "1_1") (pintype "passive"))
      (node (ref "R158") (pin "1") (pinfunction "1_1") (pintype "passive"))
    )
    (net (code "23") (name "/XO_VC") (class "Default")
      (node (ref "R149") (pin "1") (pinfunction "1_1") (pintype "passive"))
      (node (ref "R157") (pin "2") (pinfunction "2_2") (pintype "passive"))
      (node (ref "XO1") (pin "1") (pinfunction "NC/VC_1") (pintype "passive"))
      (node (ref "XO2") (pin "1") (pinfunction "VC_1") (pintype "passive"))
      (node (ref "XO3") (pin "1") (pinfunction "Vc_1") (pintype "passive"))
      (node (ref "XO4") (pin "1") (pinfunction "VCO_1") (pintype "input"))
      (node (ref "XO5") (pin "1") (pinfunction "Vcon_1") (pintype "passive"))
    )
    (net (code "24") (name "GND") (class "Default")
      (node (ref "C100") (pin "1") (pinfunction "1_1") (pintype "passive"))
      (node (ref "C101") (pin "1") (pinfunction "1_1") (pintype "passive"))
      (node (ref "C102") (pin "1") (pinfunction "1_1") (pintype "passive"))
      (node (ref "C103") (pin "1") (pinfunction "1_1") (pintype "passive"))
      (node (ref "C104") (pin "1") (pinfunction "1_1") (pintype "passive"))
      (node (ref "C105") (pin "1") (pinfunction "1_1") (pintype "passive"))
      (node (ref "C106") (pin "1") (pinfunction "1_1") (pintype "passive"))
      (node (ref "C107") (pin "1") (pinfunction "1_1") (pintype "passive"))
      (node (ref "C108") (pin "1") (pinfunction "1_1") (pintype "passive"))
      (node (ref "C109") (pin "1") (pinfunction "1_1") (pintype "passive"))
      (node (ref "C110") (pin "1") (pinfunction "1_1") (pintype "passive"))
      (node (ref "C111") (pin "2") (pinfunction "2_2") (pintype "passive"))
      (node (ref "C112") (pin "2") (pinfunction "2_2") (pintype "passive"))
      (node (ref "C115") (pin "1") (pinfunction "1_1") (pintype "passive"))
      (node (ref "C116") (pin "2") (pinfunction "2_2") (pintype "passive"))
      (node (ref "C117") (pin "2") (pinfunction "2_2") (pintype "passive"))
      (node (ref "C118") (pin "1") (pinfunction "1_1") (pintype "passive"))
      (node (ref "C119") (pin "2") (pinfunction "2_2") (pintype "passive"))
      (node (ref "C120") (pin "2") (pinfunction "2_2") (pintype "passive"))
      (node (ref "C121") (pin "1") (pinfunction "1_1") (pintype "passive"))
      (node (ref "C122") (pin "2") (pinfunction "2_2") (pintype "passive"))
      (node (ref "C123") (pin "2") (pinfunction "2_2") (pintype "passive"))
      (node (ref "C126") (pin "1") (pinfunction "1_1") (pintype "passive"))
      (node (ref "C127") (pin "2") (pinfunction "2_2") (pintype "passive"))
      (node (ref "C128") (pin "1") (pinfunction "1_1") (pintype "passive"))
      (node (ref "C130") (pin "1") (pinfunction "1_1") (pintype "passive"))
      (node (ref "C131") (pin "2") (pinfunction "2_2") (pintype "passive"))
      (node (ref "C132") (pin "2") (pinfunction "2_2") (pintype "passive"))
      (node (ref "C133") (pin "2") (pinfunction "2_2") (pintype "passive"))
      (node (ref "C84") (pin "1") (pinfunction "1_1") (pintype "passive"))
      (node (ref "C85") (pin "1") (pinfunction "1_1") (pintype "passive"))
      (node (ref "C86") (pin "2") (pinfunction "2_2") (pintype "passive"))
      (node (ref "C89") (pin "1") (pinfunction "1_1") (pintype "passive"))
      (node (ref "C90") (pin "1") (pinfunction "1_1") (pintype "passive"))
      (node (ref "C91") (pin "1") (pinfunction "1_1") (pintype "passive"))
      (node (ref "C92") (pin "1") (pinfunction "1_1") (pintype "passive"))
      (node (ref "C93") (pin "1") (pinfunction "1_1") (pintype "passive"))
      (node (ref "C94") (pin "1") (pinfunction "1_1") (pintype "passive"))
      (node (ref "C95") (pin "1") (pinfunction "1_1") (pintype "passive"))
      (node (ref "C96") (pin "1") (pinfunction "1_1") (pintype "passive"))
      (node (ref "C97") (pin "1") (pinfunction "1_1") (pintype "passive"))
      (node (ref "C98") (pin "1") (pinfunction "1_1") (pintype "passive"))
      (node (ref "C99") (pin "1") (pinfunction "1_1") (pintype "passive"))
      (node (ref "IC24") (pin "1") (pinfunction "GND_1") (pintype "passive"))
      (node (ref "IC24") (pin "11") (pinfunction "GND_11") (pintype "passive"))
      (node (ref "IC24") (pin "12") (pinfunction "GND_12") (pintype "passive"))
      (node (ref "IC24") (pin "16") (pinfunction "GND_16") (pintype "passive"))
      (node (ref "IC24") (pin "19") (pinfunction "GND_19") (pintype "passive"))
      (node (ref "IC24") (pin "22") (pinfunction "SEL_22") (pintype "passive"))
      (node (ref "IC24") (pin "25") (pinfunction "GND_25") (pintype "passive"))
      (node (ref "IC24") (pin "7") (pinfunction "GND_7") (pintype "passive"))
      (node (ref "IC25") (pin "2") (pinfunction "GND_2") (pintype "passive"))
      (node (ref "IC26") (pin "8") (pinfunction "GND_8") (pintype "passive"))
      (node (ref "IC27") (pin "1") (pinfunction "CPGND_1") (pintype "passive"))
      (node (ref "IC27") (pin "10") (pinfunction "DGND_10") (pintype "passive"))
      (node (ref "IC27") (pin "2") (pinfunction "AGND_2") (pintype "passive"))
      (node (ref "IC27") (pin "21") (pinfunction "AGND_21") (pintype "passive"))
      (node (ref "IC27") (pin "3") (pinfunction "AGND_3") (pintype "passive"))
      (node (ref "IC27") (pin "9") (pinfunction "DGND_9") (pintype "passive"))
      (node (ref "IC28") (pin "5") (pinfunction "GND_5") (pintype "power_in"))
      (node (ref "J32") (pin "2") (pinfunction "Y_2") (pintype "passive"))
      (node (ref "J33") (pin "2") (pinfunction "Y_2") (pintype "passive"))
      (node (ref "J35") (pin "2") (pinfunction "Y_2") (pintype "passive"))
      (node (ref "R136") (pin "1") (pinfunction "1_1") (pintype "passive"))
      (node (ref "R150") (pin "1") (pinfunction "1_1") (pintype "passive"))
      (node (ref "R156") (pin "1") (pinfunction "1_1") (pintype "passive"))
      (node (ref "R158") (pin "2") (pinfunction "2_2") (pintype "passive"))
      (node (ref "R159") (pin "2") (pinfunction "2_2") (pintype "passive"))
      (node (ref "R160") (pin "2") (pinfunction "2_2") (pintype "passive"))
      (node (ref "R161") (pin "1") (pinfunction "1_1") (pintype "passive"))
      (node (ref "R166") (pin "2") (pinfunction "2_2") (pintype "passive"))
      (node (ref "XO1") (pin "2") (pinfunction "GND_2") (pintype "passive"))
      (node (ref "XO2") (pin "2") (pinfunction "GND_2") (pintype "passive"))
      (node (ref "XO3") (pin "2") (pinfunction "GND_2") (pintype "passive"))
      (node (ref "XO4") (pin "4") (pinfunction "GND_4") (pintype "passive"))
      (node (ref "XO5") (pin "2") (pinfunction "GND_2") (pintype "passive"))
    )
    (net (code "25") (name "Net-(C87-Pad2)") (class "Default")
      (node (ref "C87") (pin "2") (pinfunction "2_2") (pintype "passive"))
      (node (ref "C88") (pin "1") (pinfunction "1_1") (pintype "passive"))
      (node (ref "R136") (pin "2") (pinfunction "2_2") (pintype "passive"))
    )
    (net (code "26") (name "Net-(C88-Pad2)") (class "Default")
      (node (ref "C88") (pin "2") (pinfunction "2_2") (pintype "passive"))
      (node (ref "R132") (pin "1") (pinfunction "1_1") (pintype "passive"))
      (node (ref "R138") (pin "1") (pinfunction "1_1") (pintype "passive"))
      (node (ref "R142") (pin "2") (pinfunction "2_2") (pintype "passive"))
      (node (ref "R145") (pin "1") (pinfunction "1_1") (pintype "passive"))
    )
    (net (code "27") (name "Net-(C110-Pad2)") (class "Default")
      (node (ref "C110") (pin "2") (pinfunction "2_2") (pintype "passive"))
      (node (ref "C111") (pin "1") (pinfunction "1_1") (pintype "passive"))
      (node (ref "C112") (pin "1") (pinfunction "1_1") (pintype "passive"))
      (node (ref "FR7") (pin "2") (pinfunction "2_2") (pintype "passive"))
      (node (ref "IC27") (pin "6") (pinfunction "AVdd_6") (pintype "passive"))
      (node (ref "IC27") (pin "7") (pinfunction "AVdd_7") (pintype "passive"))
    )
    (net (code "28") (name "Net-(C113-Pad2)") (class "Default")
      (node (ref "C113") (pin "2") (pinfunction "2_2") (pintype "passive"))
      (node (ref "C114") (pin "1") (pinfunction "1_1") (pintype "passive"))
      (node (ref "R150") (pin "2") (pinfunction "2_2") (pintype "passive"))
    )
    (net (code "29") (name "Net-(C118-Pad2)") (class "Default")
      (node (ref "C118") (pin "2") (pinfunction "2_2") (pintype "passive"))
      (node (ref "R148") (pin "1") (pinfunction "1_1") (pintype "passive"))
      (node (ref "R149") (pin "2") (pinfunction "2_2") (pintype "passive"))
      (node (ref "R163") (pin "1") (pinfunction "1_1") (pintype "passive"))
      (node (ref "R166") (pin "1") (pinfunction "1_1") (pintype "passive"))
    )
    (net (code "30") (name "Net-(C124-Pad2)") (class "Default")
      (node (ref "C124") (pin "2") (pinfunction "2_2") (pintype "passive"))
      (node (ref "C125") (pin "1") (pinfunction "1_1") (pintype "passive"))
      (node (ref "R156") (pin "2") (pinfunction "2_2") (pintype "passive"))
    )
    (net (code "31") (name "Net-(C128-Pad2)") (class "Default")
      (node (ref "C128") (pin "2") (pinfunction "2_2") (pintype "passive"))
      (node (ref "R155") (pin "2") (pinfunction "2_2") (pintype "passive"))
      (node (ref "R157") (pin "1") (pinfunction "1_1") (pintype "passive"))
    )
    (net (code "32") (name "Net-(C129-Pad1)") (class "Default")
      (node (ref "C129") (pin "1") (pinfunction "1_1") (pintype "passive"))
      (node (ref "R161") (pin "2") (pinfunction "2_2") (pintype "passive"))
    )
    (net (code "33") (name "Net-(FR4-Pad2)") (class "Default")
      (node (ref "FR4") (pin "2") (pinfunction "2_2") (pintype "passive"))
      (node (ref "R133") (pin "1") (pinfunction "1_1") (pintype "passive"))
      (node (ref "R139") (pin "2") (pinfunction "2_2") (pintype "passive"))
      (node (ref "R140") (pin "1") (pinfunction "1_1") (pintype "passive"))
      (node (ref "R144") (pin "1") (pinfunction "1_1") (pintype "passive"))
    )
    (net (code "34") (name "Net-(IC24-CLKin)") (class "Default")
      (node (ref "C87") (pin "1") (pinfunction "1_1") (pintype "passive"))
      (node (ref "IC24") (pin "21") (pinfunction "CLKin_21") (pintype "passive"))
    )
    (net (code "35") (name "Net-(IC24-CLKin*)") (class "Default")
      (node (ref "C89") (pin "2") (pinfunction "2_2") (pintype "passive"))
      (node (ref "IC24") (pin "20") (pinfunction "CLKin*_20") (pintype "passive"))
    )
    (net (code "36") (name "Net-(IC24-OE)") (class "Default")
      (node (ref "IC24") (pin "24") (pinfunction "OE_24") (pintype "passive"))
      (node (ref "R134") (pin "1") (pinfunction "1_1") (pintype "passive"))
    )
    (net (code "37") (name "Net-(IC25-EN)") (class "Default")
      (node (ref "C105") (pin "2") (pinfunction "2_2") (pintype "passive"))
      (node (ref "C107") (pin "2") (pinfunction "2_2") (pintype "passive"))
      (node (ref "IC25") (pin "1") (pinfunction "IN_1") (pintype "input"))
      (node (ref "IC25") (pin "3") (pinfunction "EN_3") (pintype "input"))
      (node (ref "R144") (pin "2") (pinfunction "2_2") (pintype "passive"))
      (node (ref "R146") (pin "2") (pinfunction "2_2") (pintype "passive"))
    )
    (net (code "38") (name "Net-(IC25-OUT)") (class "Default")
      (node (ref "C106") (pin "2") (pinfunction "2_2") (pintype "passive"))
      (node (ref "C108") (pin "2") (pinfunction "2_2") (pintype "passive"))
      (node (ref "IC25") (pin "5") (pinfunction "OUT_5") (pintype "output"))
      (node (ref "R146") (pin "1") (pinfunction "1_1") (pintype "passive"))
      (node (ref "XO5") (pin "4") (pinfunction "VCC_4") (pintype "passive"))
    )
    (net (code "39") (name "Net-(IC26-Vdd)") (class "Default")
      (node (ref "C115") (pin "2") (pinfunction "2_2") (pintype "passive"))
      (node (ref "C116") (pin "1") (pinfunction "1_1") (pintype "passive"))
      (node (ref "C117") (pin "1") (pinfunction "1_1") (pintype "passive"))
      (node (ref "C133") (pin "1") (pinfunction "1_1") (pintype "passive"))
      (node (ref "FR8") (pin "1") (pinfunction "1_1") (pintype "passive"))
      (node (ref "IC26") (pin "1") (pinfunction "Vdd_1") (pintype "power_in"))
      (node (ref "IC28") (pin "4") (pinfunction "VDD_4") (pintype "power_in"))
      (node (ref "R153") (pin "2") (pinfunction "2_2") (pintype "passive"))
    )
    (net (code "40") (name "Net-(IC26-Vfb)") (class "Default")
      (node (ref "C122") (pin "1") (pinfunction "1_1") (pintype "passive"))
      (node (ref "IC26") (pin "3") (pinfunction "Vfb_3") (pintype "input"))
      (node (ref "IC26") (pin "4") (pinfunction "Vout_4") (pintype "output"))
      (node (ref "R148") (pin "2") (pinfunction "2_2") (pintype "passive"))
    )
    (net (code "41") (name "Net-(IC27-CE)") (class "Default")
      (node (ref "IC27") (pin "11") (pinfunction "CE_11") (pintype "passive"))
      (node (ref "R154") (pin "1") (pinfunction "1_1") (pintype "passive"))
    )
    (net (code "42") (name "Net-(IC27-CLK)") (class "Default")
      (node (ref "C132") (pin "1") (pinfunction "1_1") (pintype "passive"))
      (node (ref "IC27") (pin "12") (pinfunction "CLK_12") (pintype "passive"))
      (node (ref "R162") (pin "2") (pinfunction "2_2") (pintype "passive"))
    )
    (net (code "43") (name "Net-(IC27-CP)") (class "Default")
      (node (ref "C129") (pin "2") (pinfunction "2_2") (pintype "passive"))
      (node (ref "C130") (pin "2") (pinfunction "2_2") (pintype "passive"))
      (node (ref "IC27") (pin "20") (pinfunction "CP_20") (pintype "passive"))
      (node (ref "R155") (pin "1") (pinfunction "1_1") (pintype "passive"))
    )
    (net (code "44") (name "Net-(IC27-DATA)") (class "Default")
      (node (ref "IC27") (pin "13") (pinfunction "DATA_13") (pintype "passive"))
      (node (ref "R164") (pin "2") (pinfunction "2_2") (pintype "passive"))
    )
    (net (code "45") (name "Net-(IC27-LE)") (class "Default")
      (node (ref "IC27") (pin "14") (pinfunction "LE_14") (pintype "passive"))
      (node (ref "R165") (pin "2") (pinfunction "2_2") (pintype "passive"))
    )
    (net (code "46") (name "Net-(IC27-REFin)") (class "Default")
      (node (ref "C124") (pin "1") (pinfunction "1_1") (pintype "passive"))
      (node (ref "IC27") (pin "8") (pinfunction "REFin_8") (pintype "passive"))
    )
    (net (code "47") (name "Net-(IC27-RFinA)") (class "Default")
      (node (ref "C113") (pin "1") (pinfunction "1_1") (pintype "passive"))
      (node (ref "IC27") (pin "5") (pinfunction "RFinA_5") (pintype "passive"))
    )
    (net (code "48") (name "Net-(IC27-RFinB)") (class "Default")
      (node (ref "C131") (pin "1") (pinfunction "1_1") (pintype "passive"))
      (node (ref "IC27") (pin "4") (pinfunction "RFinB_4") (pintype "passive"))
    )
    (net (code "49") (name "Net-(IC27-Rset)") (class "Default")
      (node (ref "IC27") (pin "19") (pinfunction "Rset_19") (pintype "passive"))
      (node (ref "R160") (pin "1") (pinfunction "1_1") (pintype "passive"))
    )
    (net (code "50") (name "Net-(IC27-Vp)") (class "Default")
      (node (ref "C121") (pin "2") (pinfunction "2_2") (pintype "passive"))
      (node (ref "C123") (pin "1") (pinfunction "1_1") (pintype "passive"))
      (node (ref "IC27") (pin "18") (pinfunction "Vp_18") (pintype "passive"))
      (node (ref "R151") (pin "1") (pinfunction "1_1") (pintype "passive"))
    )
    (net (code "51") (name "Net-(IC28-VOUT)") (class "Default")
      (node (ref "IC28") (pin "6") (pinfunction "VOUT_6") (pintype "tri_state"))
      (node (ref "R163") (pin "2") (pinfunction "2_2") (pintype "passive"))
    )
    (net (code "52") (name "Net-(J33-X)") (class "Default")
      (node (ref "J33") (pin "1") (pinfunction "X_1") (pintype "passive"))
      (node (ref "R135") (pin "1") (pinfunction "1_1") (pintype "passive"))
    )
    (net (code "53") (name "Net-(J37-Pad2)") (class "Default")
      (node (ref "J37") (pin "2") (pinfunction "2_2") (pintype "passive"))
      (node (ref "R141") (pin "1") (pinfunction "1_1") (pintype "passive"))
    )
    (net (code "54") (name "Net-(R140-Pad2)") (class "Default")
      (node (ref "R140") (pin "2") (pinfunction "2_2") (pintype "passive"))
      (node (ref "R143") (pin "1") (pinfunction "1_1") (pintype "passive"))
    )
    (net (code "55") (name "Net-(XO1-Output)") (class "Default")
      (node (ref "R132") (pin "2") (pinfunction "2_2") (pintype "passive"))
      (node (ref "XO1") (pin "3") (pinfunction "Output_3") (pintype "output"))
    )
    (net (code "56") (name "Net-(XO1-Vcc)") (class "Default")
      (node (ref "C84") (pin "2") (pinfunction "2_2") (pintype "passive"))
      (node (ref "C85") (pin "2") (pinfunction "2_2") (pintype "passive"))
      (node (ref "C86") (pin "1") (pinfunction "1_1") (pintype "passive"))
      (node (ref "R133") (pin "2") (pinfunction "2_2") (pintype "passive"))
      (node (ref "XO1") (pin "4") (pinfunction "Vcc_4") (pintype "power_in"))
    )
    (net (code "57") (name "Net-(XO2-OUT)") (class "Default")
      (node (ref "R138") (pin "2") (pinfunction "2_2") (pintype "passive"))
      (node (ref "XO2") (pin "4") (pinfunction "OUT_4") (pintype "passive"))
      (node (ref "XO3") (pin "3") (pinfunction "OUT_3") (pintype "passive"))
    )
    (net (code "58") (name "Net-(XO2-TRI-ST.)") (class "Default")
      (node (ref "R137") (pin "1") (pinfunction "1_1") (pintype "passive"))
      (node (ref "XO2") (pin "6") (pinfunction "TRI-ST._6") (pintype "passive"))
    )
    (net (code "59") (name "Net-(XO2-VDD)") (class "Default")
      (node (ref "C90") (pin "2") (pinfunction "2_2") (pintype "passive"))
      (node (ref "C91") (pin "2") (pinfunction "2_2") (pintype "passive"))
      (node (ref "R137") (pin "2") (pinfunction "2_2") (pintype "passive"))
      (node (ref "R139") (pin "1") (pinfunction "1_1") (pintype "passive"))
      (node (ref "XO2") (pin "5") (pinfunction "VDD_5") (pintype "passive"))
      (node (ref "XO3") (pin "4") (pinfunction "VDD_4") (pintype "passive"))
    )
    (net (code "60") (name "Net-(XO4-RF_OUT)") (class "Default")
      (node (ref "R142") (pin "1") (pinfunction "1_1") (pintype "passive"))
      (node (ref "XO4") (pin "6") (pinfunction "RF_OUT_6") (pintype "output"))
    )
    (net (code "61") (name "Net-(XO4-VCC)") (class "Default")
      (node (ref "C96") (pin "2") (pinfunction "2_2") (pintype "passive"))
      (node (ref "C97") (pin "2") (pinfunction "2_2") (pintype "passive"))
      (node (ref "R143") (pin "2") (pinfunction "2_2") (pintype "passive"))
      (node (ref "XO4") (pin "9") (pinfunction "VCC_9") (pintype "power_in"))
    )
    (net (code "62") (name "Net-(XO4-VC_FILTER)") (class "Default")
      (node (ref "C98") (pin "2") (pinfunction "2_2") (pintype "passive"))
      (node (ref "XO4") (pin "7") (pinfunction "VC_FILTER_7") (pintype "input"))
    )
    (net (code "63") (name "Net-(XO5-OUT)") (class "Default")
      (node (ref "R145") (pin "2") (pinfunction "2_2") (pintype "passive"))
      (node (ref "R147") (pin "1") (pinfunction "1_1") (pintype "passive"))
      (node (ref "XO5") (pin "3") (pinfunction "OUT_3") (pintype "passive"))
    )
    (net (code "64") (name "VCC2P5_VREF") (class "Default")
      (node (ref "R152") (pin "2") (pinfunction "2_2") (pintype "passive"))
    )
    (net (code "65") (name "VCC3P3_CLK") (class "Default")
      (node (ref "C109") (pin "2") (pinfunction "2_2") (pintype "passive"))
      (node (ref "C119") (pin "1") (pinfunction "1_1") (pintype "passive"))
      (node (ref "C120") (pin "1") (pinfunction "1_1") (pintype "passive"))
      (node (ref "FR4") (pin "1") (pinfunction "1_1") (pintype "passive"))
      (node (ref "FR5") (pin "1") (pinfunction "1_1") (pintype "passive"))
      (node (ref "FR6") (pin "1") (pinfunction "1_1") (pintype "passive"))
      (node (ref "FR7") (pin "1") (pinfunction "1_1") (pintype "passive"))
      (node (ref "FR8") (pin "2") (pinfunction "2_2") (pintype "passive"))
      (node (ref "IC27") (pin "16") (pinfunction "DVdd_16") (pintype "passive"))
      (node (ref "IC27") (pin "17") (pinfunction "DVdd_17") (pintype "passive"))
      (node (ref "R151") (pin "2") (pinfunction "2_2") (pintype "passive"))
      (node (ref "R154") (pin "2") (pinfunction "2_2") (pintype "passive"))
    )
    (net (code "66") (name "VCC3P3_LMK") (class "Default")
      (node (ref "C92") (pin "2") (pinfunction "2_2") (pintype "passive"))
      (node (ref "C93") (pin "2") (pinfunction "2_2") (pintype "passive"))
      (node (ref "C94") (pin "2") (pinfunction "2_2") (pintype "passive"))
      (node (ref "C95") (pin "2") (pinfunction "2_2") (pintype "passive"))
      (node (ref "FR5") (pin "2") (pinfunction "2_2") (pintype "passive"))
      (node (ref "IC24") (pin "23") (pinfunction "Vdd_23") (pintype "passive"))
      (node (ref "IC24") (pin "8") (pinfunction "Vdd_8") (pintype "passive"))
      (node (ref "R134") (pin "2") (pinfunction "2_2") (pintype "passive"))
    )
    (net (code "67") (name "VCC3P3_LMK_VDDO") (class "Default")
      (node (ref "C100") (pin "2") (pinfunction "2_2") (pintype "passive"))
      (node (ref "C101") (pin "2") (pinfunction "2_2") (pintype "passive"))
      (node (ref "C102") (pin "2") (pinfunction "2_2") (pintype "passive"))
      (node (ref "C103") (pin "2") (pinfunction "2_2") (pintype "passive"))
      (node (ref "C104") (pin "2") (pinfunction "2_2") (pintype "passive"))
      (node (ref "C99") (pin "2") (pinfunction "2_2") (pintype "passive"))
      (node (ref "FR6") (pin "2") (pinfunction "2_2") (pintype "passive"))
      (node (ref "IC24") (pin "14") (pinfunction "Vddo_14") (pintype "passive"))
      (node (ref "IC24") (pin "18") (pinfunction "Vddo_18") (pintype "passive"))
      (node (ref "IC24") (pin "2") (pinfunction "Vddo_2") (pintype "passive"))
      (node (ref "IC24") (pin "6") (pinfunction "Vddo_6") (pintype "passive"))
    )
    (net (code "68") (name "unconnected-(IC24-CLKout4-Pad17)") (class "Default")
      (node (ref "IC24") (pin "17") (pinfunction "CLKout4_17") (pintype "passive+no_connect"))
    )
    (net (code "69") (name "unconnected-(IC24-OSCin-Pad9)") (class "Default")
      (node (ref "IC24") (pin "9") (pinfunction "OSCin_9") (pintype "passive+no_connect"))
    )
    (net (code "70") (name "unconnected-(IC24-OSCout-Pad10)") (class "Default")
      (node (ref "IC24") (pin "10") (pinfunction "OSCout_10") (pintype "passive+no_connect"))
    )
    (net (code "71") (name "unconnected-(IC25-NC-Pad4)") (class "Default")
      (node (ref "IC25") (pin "4") (pinfunction "NC_4") (pintype "passive+no_connect"))
    )
    (net (code "72") (name "unconnected-(JMP2-Pad1)") (class "Default")
      (node (ref "JMP2") (pin "1") (pinfunction "1_1") (pintype "passive"))
    )
    (net (code "73") (name "unconnected-(JMP2-Pad2)") (class "Default")
      (node (ref "JMP2") (pin "2") (pinfunction "2_2") (pintype "passive"))
    )
    (net (code "74") (name "unconnected-(JMP3-Pad1)") (class "Default")
      (node (ref "JMP3") (pin "1") (pinfunction "1_1") (pintype "passive"))
    )
    (net (code "75") (name "unconnected-(JMP3-Pad2)") (class "Default")
      (node (ref "JMP3") (pin "2") (pinfunction "2_2") (pintype "passive"))
    )
    (net (code "76") (name "unconnected-(JMP4-Pad1)") (class "Default")
      (node (ref "JMP4") (pin "1") (pinfunction "1_1") (pintype "passive"))
    )
    (net (code "77") (name "unconnected-(JMP4-Pad2)") (class "Default")
      (node (ref "JMP4") (pin "2") (pinfunction "2_2") (pintype "passive"))
    )
    (net (code "78") (name "unconnected-(JMP5-Pad1)") (class "Default")
      (node (ref "JMP5") (pin "1") (pinfunction "1_1") (pintype "passive"))
    )
    (net (code "79") (name "unconnected-(JMP5-Pad2)") (class "Default")
      (node (ref "JMP5") (pin "2") (pinfunction "2_2") (pintype "passive"))
    )
    (net (code "80") (name "unconnected-(JMP6-Pad1)") (class "Default")
      (node (ref "JMP6") (pin "1") (pinfunction "1_1") (pintype "passive"))
    )
    (net (code "81") (name "unconnected-(JMP6-Pad2)") (class "Default")
      (node (ref "JMP6") (pin "2") (pinfunction "2_2") (pintype "passive"))
    )
    (net (code "82") (name "unconnected-(XO2-T.S.-Pad3)") (class "Default")
      (node (ref "XO2") (pin "3") (pinfunction "T.S._3") (pintype "passive+no_connect"))
    )
    (net (code "83") (name "unconnected-(XO4-NC-Pad2)") (class "Default")
      (node (ref "XO4") (pin "2") (pinfunction "NC_2") (pintype "passive+no_connect"))
    )
    (net (code "84") (name "unconnected-(XO4-NC-Pad3)") (class "Default")
      (node (ref "XO4") (pin "3") (pinfunction "NC_3") (pintype "passive+no_connect"))
    )
    (net (code "85") (name "unconnected-(XO4-NC-Pad5)") (class "Default")
      (node (ref "XO4") (pin "5") (pinfunction "NC_5") (pintype "passive+no_connect"))
    )
    (net (code "86") (name "unconnected-(XO4-NC-Pad8)") (class "Default")
      (node (ref "XO4") (pin "8") (pinfunction "NC_8") (pintype "passive+no_connect"))
    )
    (net (code "87") (name "unconnected-(XO4-NC-Pad10)") (class "Default")
      (node (ref "XO4") (pin "10") (pinfunction "NC_10") (pintype "passive+no_connect"))
    )
  )
)
